# MIC.net
KiCad netlist of a schematic drawn in EAGLE
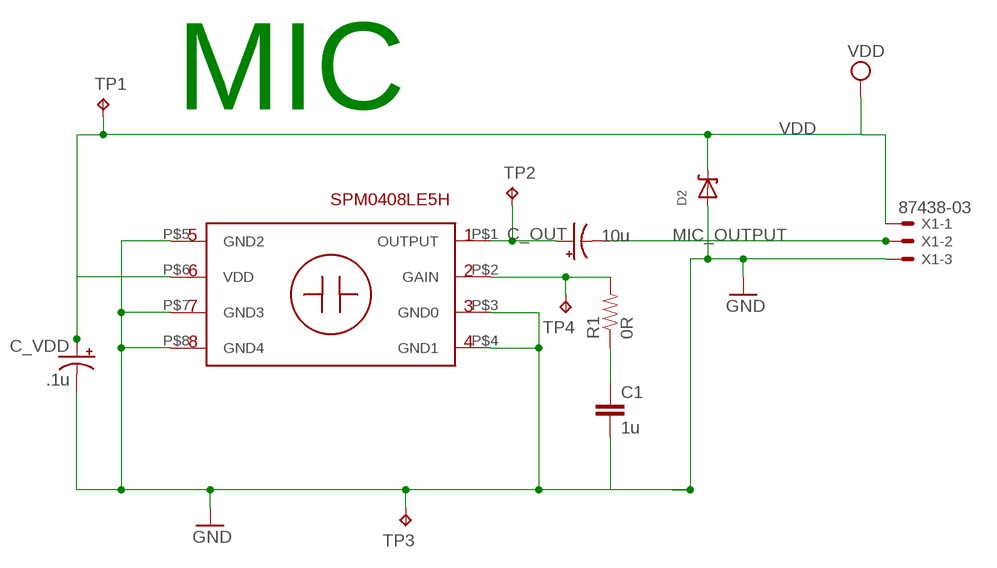
[diagram p0: schematic, sheet 1]

(export (version "E")
  (design (tool "Eeschema 10.0.6"))
  (components
    (comp (ref "C1")
      (value "1u")
      (footprint "eagle-import:0402")
      (libsource (lib "eagle-import") (part "CAP_0402"))
    )
    (comp (ref "C_OUT")
      (value "10u")
      (footprint "eagle-import:EIA3216-KIT")
      (fields (field (name "MF") "AVX") (field (name "MPN") "0603ZD106MAT2A"))
      (libsource (lib "eagle-import") (part "CAP_POL1206-KIT"))
    )
    (comp (ref "C_VDD")
      (value ".1u")
      (footprint "eagle-import:EIA3216-KIT")
      (fields (field (name "MF") "VISHAY SPRAGUE") (field (name "MPN") "293D106X96R3A2TE3"))
      (libsource (lib "eagle-import") (part "CAP_POL1206-KIT"))
    )
    (comp (ref "D2")
      (value "DIODE-ZENERSOD123")
      (footprint "eagle-import:SOD-123")
      (libsource (lib "eagle-import") (part "DIODE-ZENERSOD123"))
    )
    (comp (ref "R1")
      (value "0R")
      (footprint "eagle-import:0402")
      (libsource (lib "eagle-import") (part "RES_0402"))
    )
    (comp (ref "TP1")
      (value "TPPAD1-17")
      (footprint "eagle-import:P1-17")
      (libsource (lib "eagle-import") (part "TPPAD1-17"))
    )
    (comp (ref "TP2")
      (value "TPPAD1-17")
      (footprint "eagle-import:P1-17")
      (libsource (lib "eagle-import") (part "TPPAD1-17"))
    )
    (comp (ref "TP3")
      (value "TPPAD1-17")
      (footprint "eagle-import:P1-17")
      (libsource (lib "eagle-import") (part "TPPAD1-17"))
    )
    (comp (ref "TP4")
      (value "TPPAD1-17")
      (footprint "eagle-import:P1-17")
      (libsource (lib "eagle-import") (part "TPPAD1-17"))
    )
    (comp (ref "U2")
      (value "SPM0408LE5H")
      (footprint "eagle-import:SPM0408LE5H-TB")
      (libsource (lib "eagle-import") (part "SPM0408LE5H"))
    )
    (comp (ref "X1")
      (value "87438-03")
      (footprint "eagle-import:87438-03")
      (fields (field (name "MF") "MOLEX"))
      (libsource (lib "eagle-import") (part "87438-03"))
    )
  )
  (nets
    (net (code "1") (name "/MIC_OUTPUT") (class "Default")
      (node (ref "C_OUT") (pin "C") (pinfunction "-_C") (pintype "passive"))
      (node (ref "X1") (pin "2") (pinfunction "S_2") (pintype "passive"))
    )
    (net (code "2") (name "GND") (class "Default")
      (node (ref "C1") (pin "2") (pinfunction "2_2") (pintype "passive"))
      (node (ref "C_VDD") (pin "C") (pinfunction "-_C") (pintype "passive"))
      (node (ref "D2") (pin "A") (pinfunction "A_A") (pintype "passive"))
      (node (ref "TP3") (pin "TP") (pinfunction "TP_TP") (pintype "input"))
      (node (ref "U2") (pin "P$3") (pinfunction "GND0_P$3") (pintype "power_in"))
      (node (ref "U2") (pin "P$4") (pinfunction "GND1_P$4") (pintype "power_in"))
      (node (ref "U2") (pin "P$5") (pinfunction "GND2_P$5") (pintype "power_in"))
      (node (ref "U2") (pin "P$7") (pinfunction "GND3_P$7") (pintype "power_in"))
      (node (ref "U2") (pin "P$8") (pinfunction "GND4_P$8") (pintype "power_in"))
      (node (ref "X1") (pin "3") (pinfunction "S_3") (pintype "passive"))
    )
    (net (code "3") (name "Net-(C1-Pad1)") (class "Default")
      (node (ref "C1") (pin "1") (pinfunction "1_1") (pintype "passive"))
      (node (ref "R1") (pin "1") (pinfunction "1_1") (pintype "passive"))
    )
    (net (code "4") (name "Net-(C_OUT-+)") (class "Default")
      (node (ref "C_OUT") (pin "A") (pinfunction "+_A") (pintype "passive"))
      (node (ref "TP2") (pin "TP") (pinfunction "TP_TP") (pintype "input"))
      (node (ref "U2") (pin "P$1") (pinfunction "OUTPUT_P$1") (pintype "output"))
    )
    (net (code "5") (name "Net-(U2-GAIN)") (class "Default")
      (node (ref "R1") (pin "2") (pinfunction "2_2") (pintype "passive"))
      (node (ref "TP4") (pin "TP") (pinfunction "TP_TP") (pintype "input"))
      (node (ref "U2") (pin "P$2") (pinfunction "GAIN_P$2") (pintype "input"))
    )
    (net (code "6") (name "VDD") (class "Default")
      (node (ref "C_VDD") (pin "A") (pinfunction "+_A") (pintype "passive"))
      (node (ref "D2") (pin "C") (pinfunction "C_C") (pintype "passive"))
      (node (ref "TP1") (pin "TP") (pinfunction "TP_TP") (pintype "input"))
      (node (ref "U2") (pin "P$6") (pinfunction "VDD_P$6") (pintype "power_in"))
      (node (ref "X1") (pin "1") (pinfunction "S_1") (pintype "passive"))
    )
  )
)
